# ROBOT_SENSORS.net
KiCad netlist of a schematic drawn in EasyEDA
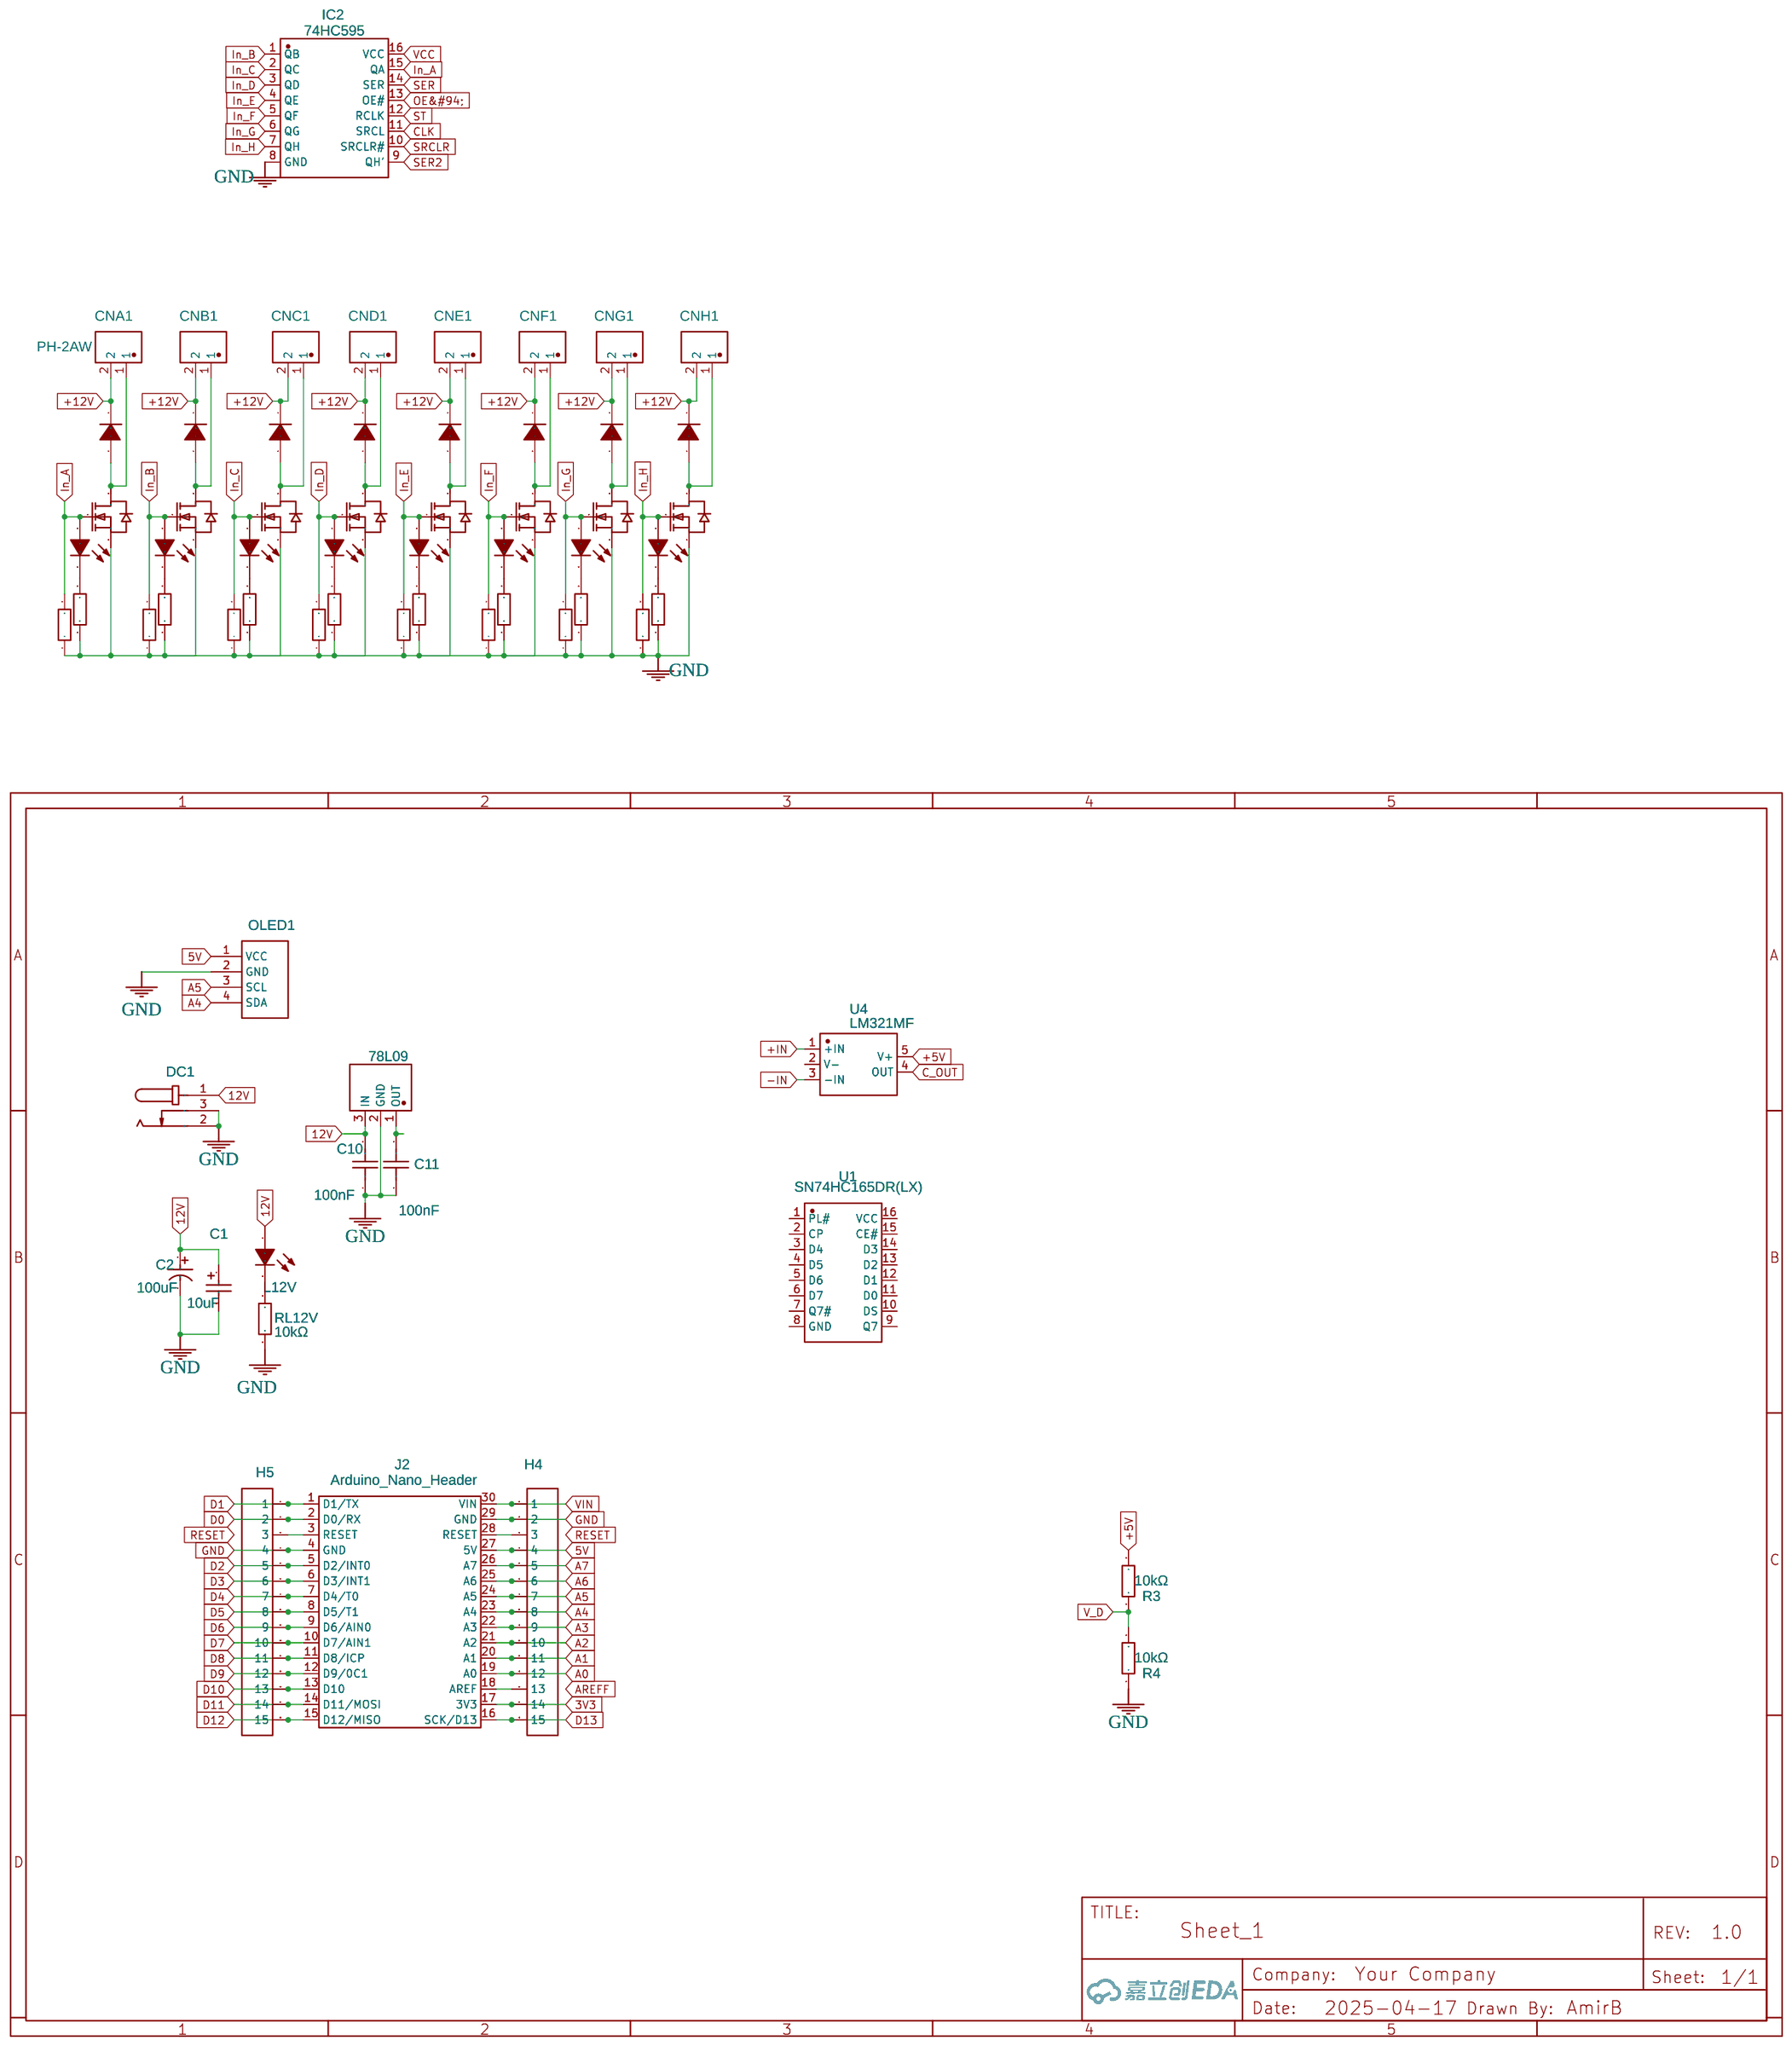
[diagram p0: schematic sheet]

(export (version "E")
  (design (tool "Eeschema 10.0.6"))
  (components
    (comp (ref "AD1")
      (value "D")
      (fields (field (name "BOM_Manufacturer Part") "ES1J") (field (name "BOM_Supplier Part") "C115404"))
      (libsource (lib "") (part "1N4007F_3"))
    )
    (comp (ref "ALED1")
      (value "LED")
      (fields
        (field (name "BOM_Manufacturer Part") "19-217/BHC-ZL1M2RY/3T")
        (field (name "BOM_Supplier Part") "C72041")
      )
      (libsource (lib "") (part "19-217/BHC-ZL1M2RY/3T_2"))
    )
    (comp (ref "AQ1")
      (value "Q")
      (fields (field (name "BOM_Manufacturer Part") "AO3400") (field (name "BOM_Supplier Part") "C5224189"))
      (libsource (lib "") (part "JSM2302_3"))
    )
    (comp (ref "AR1")
      (value "R10K")
      (fields
        (field (name "BOM_Manufacturer Part") "0603WAF1002T5E")
        (field (name "BOM_Supplier Part") "C25804")
      )
      (libsource (lib "") (part "0603WAF1001T5E_7"))
    )
    (comp (ref "AR2")
      (value "R10K")
      (fields
        (field (name "BOM_Manufacturer Part") "0603WAF1002T5E")
        (field (name "BOM_Supplier Part") "C25804")
      )
      (libsource (lib "") (part "0603WAF1001T5E_7"))
    )
    (comp (ref "BD1")
      (value "D")
      (fields (field (name "BOM_Manufacturer Part") "ES1J") (field (name "BOM_Supplier Part") "C115404"))
      (libsource (lib "") (part "1N4007F_2"))
    )
    (comp (ref "BLED1")
      (value "LED")
      (fields
        (field (name "BOM_Manufacturer Part") "19-217/BHC-ZL1M2RY/3T")
        (field (name "BOM_Supplier Part") "C72041")
      )
      (libsource (lib "") (part "19-217/BHC-ZL1M2RY/3T_7"))
    )
    (comp (ref "BQ1")
      (value "Q")
      (fields (field (name "BOM_Manufacturer Part") "AO3400") (field (name "BOM_Supplier Part") "C5224189"))
      (libsource (lib "") (part "JSM2302"))
    )
    (comp (ref "BR1")
      (value "R10K")
      (fields
        (field (name "BOM_Manufacturer Part") "0603WAF1002T5E")
        (field (name "BOM_Supplier Part") "C25804")
      )
      (libsource (lib "") (part "0603WAF1001T5E_5"))
    )
    (comp (ref "BR2")
      (value "R10K")
      (fields
        (field (name "BOM_Manufacturer Part") "0603WAF1002T5E")
        (field (name "BOM_Supplier Part") "C25804")
      )
      (libsource (lib "") (part "0603WAF1001T5E_5"))
    )
    (comp (ref "C1")
      (value "10uF")
      (fields (field (name "Manufacturer Part") "TAJA106K016RNJ") (field (name "Manufacturer") "Kyocera AVX"))
      (libsource (lib "") (part "TAJA106K016RNJ"))
    )
    (comp (ref "C2")
      (value "100uF")
      (fields
        (field (name "Manufacturer Part") "KM107M035E11RR0VH2FP0")
        (field (name "Manufacturer") "CX(承兴)")
      )
      (libsource (lib "") (part "100uF 35V 6.3*11"))
    )
    (comp (ref "C10")
      (value "100nF")
      (fields
        (field (name "Manufacturer Part") "CC0603KRX7R9BB104")
        (field (name "Manufacturer") "YAGEO(国巨)")
      )
      (libsource (lib "") (part "CC0603KRX7R9BB104"))
    )
    (comp (ref "C11")
      (value "100nF")
      (fields
        (field (name "Manufacturer Part") "CC0603KRX7R9BB104")
        (field (name "Manufacturer") "YAGEO(国巨)")
      )
      (libsource (lib "") (part "CC0603KRX7R9BB104"))
    )
    (comp (ref "CD1")
      (value "D")
      (fields (field (name "BOM_Manufacturer Part") "ES1J") (field (name "BOM_Supplier Part") "C115404"))
      (libsource (lib "") (part "1N4007F_4"))
    )
    (comp (ref "CLED1")
      (value "LED")
      (fields
        (field (name "BOM_Manufacturer Part") "19-217/BHC-ZL1M2RY/3T")
        (field (name "BOM_Supplier Part") "C72041")
      )
      (libsource (lib "") (part "19-217/BHC-ZL1M2RY/3T_8"))
    )
    (comp (ref "CNA1")
      (value "PH-2AW")
      (fields (field (name "Manufacturer") "CAX(创都)"))
      (libsource (lib "") (part "PH-2AW_1"))
    )
    (comp (ref "CNB1")
      (value "PH-2AW")
      (fields (field (name "Manufacturer") "CAX(创都)"))
      (libsource (lib "") (part "PH-2AW_6"))
    )
    (comp (ref "CNC1")
      (value "PH-2AW")
      (fields (field (name "Manufacturer") "CAX(创都)"))
      (libsource (lib "") (part "PH-2AW_5"))
    )
    (comp (ref "CND1")
      (value "PH-2AW")
      (fields (field (name "Manufacturer") "CAX(创都)"))
      (libsource (lib "") (part "PH-2AW_3"))
    )
    (comp (ref "CNE1")
      (value "PH-2AW")
      (fields (field (name "Manufacturer") "CAX(创都)"))
      (libsource (lib "") (part "PH-2AW_2"))
    )
    (comp (ref "CNF1")
      (value "PH-2AW")
      (fields (field (name "Manufacturer") "CAX(创都)"))
      (libsource (lib "") (part "PH-2AW_7"))
    )
    (comp (ref "CNG1")
      (value "PH-2AW")
      (fields (field (name "Manufacturer") "CAX(创都)"))
      (libsource (lib "") (part "PH-2AW_4"))
    )
    (comp (ref "CNH1")
      (value "PH-2AW")
      (fields (field (name "Manufacturer") "CAX(创都)"))
      (libsource (lib "") (part "PH-2AW"))
    )
    (comp (ref "CQ1")
      (value "Q")
      (fields (field (name "BOM_Manufacturer Part") "AO3400") (field (name "BOM_Supplier Part") "C5224189"))
      (libsource (lib "") (part "JSM2302_5"))
    )
    (comp (ref "CR1")
      (value "R10K")
      (fields
        (field (name "BOM_Manufacturer Part") "0603WAF1002T5E")
        (field (name "BOM_Supplier Part") "C25804")
      )
      (libsource (lib "") (part "0603WAF1001T5E_6"))
    )
    (comp (ref "CR2")
      (value "R10K")
      (fields
        (field (name "BOM_Manufacturer Part") "0603WAF1002T5E")
        (field (name "BOM_Supplier Part") "C25804")
      )
      (libsource (lib "") (part "0603WAF1001T5E_6"))
    )
    (comp (ref "DC1")
      (value "DC")
      (fields
        (field (name "BOM_Manufacturer Part") "DC005-2.0MM")
        (field (name "BOM_Supplier Part") "C111567")
      )
      (libsource (lib "") (part "DC005-2.0MM"))
    )
    (comp (ref "DD1")
      (value "D")
      (fields (field (name "BOM_Manufacturer Part") "ES1J") (field (name "BOM_Supplier Part") "C115404"))
      (libsource (lib "") (part "1N4007F_6"))
    )
    (comp (ref "DLED1")
      (value "LED")
      (fields
        (field (name "BOM_Manufacturer Part") "19-217/BHC-ZL1M2RY/3T")
        (field (name "BOM_Supplier Part") "C72041")
      )
      (libsource (lib "") (part "19-217/BHC-ZL1M2RY/3T_4"))
    )
    (comp (ref "DQ1")
      (value "Q")
      (fields (field (name "BOM_Manufacturer Part") "AO3400") (field (name "BOM_Supplier Part") "C5224189"))
      (libsource (lib "") (part "JSM2302_2"))
    )
    (comp (ref "DR1")
      (value "R10K")
      (fields
        (field (name "BOM_Manufacturer Part") "0603WAF1002T5E")
        (field (name "BOM_Supplier Part") "C25804")
      )
      (libsource (lib "") (part "0603WAF1001T5E_4"))
    )
    (comp (ref "DR2")
      (value "R10K")
      (fields
        (field (name "BOM_Manufacturer Part") "0603WAF1002T5E")
        (field (name "BOM_Supplier Part") "C25804")
      )
      (libsource (lib "") (part "0603WAF1001T5E_4"))
    )
    (comp (ref "ED1")
      (value "D")
      (fields (field (name "BOM_Manufacturer Part") "ES1J") (field (name "BOM_Supplier Part") "C115404"))
      (libsource (lib "") (part "1N4007F_1"))
    )
    (comp (ref "ELED1")
      (value "LED")
      (fields
        (field (name "BOM_Manufacturer Part") "19-217/BHC-ZL1M2RY/3T")
        (field (name "BOM_Supplier Part") "C72041")
      )
      (libsource (lib "") (part "19-217/BHC-ZL1M2RY/3T_5"))
    )
    (comp (ref "EQ1")
      (value "Q")
      (fields (field (name "BOM_Manufacturer Part") "AO3400") (field (name "BOM_Supplier Part") "C5224189"))
      (libsource (lib "") (part "JSM2302_1"))
    )
    (comp (ref "ER1")
      (value "R10K")
      (fields
        (field (name "BOM_Manufacturer Part") "0603WAF1002T5E")
        (field (name "BOM_Supplier Part") "C25804")
      )
      (libsource (lib "") (part "0603WAF1001T5E_1"))
    )
    (comp (ref "ER2")
      (value "R10K")
      (fields
        (field (name "BOM_Manufacturer Part") "0603WAF1002T5E")
        (field (name "BOM_Supplier Part") "C25804")
      )
      (libsource (lib "") (part "0603WAF1001T5E_1"))
    )
    (comp (ref "FD1")
      (value "D")
      (fields (field (name "BOM_Manufacturer Part") "ES1J") (field (name "BOM_Supplier Part") "C115404"))
      (libsource (lib "") (part "1N4007F_5"))
    )
    (comp (ref "FLED1")
      (value "LED")
      (fields
        (field (name "BOM_Manufacturer Part") "19-217/BHC-ZL1M2RY/3T")
        (field (name "BOM_Supplier Part") "C72041")
      )
      (libsource (lib "") (part "19-217/BHC-ZL1M2RY/3T"))
    )
    (comp (ref "FQ1")
      (value "Q")
      (fields (field (name "BOM_Manufacturer Part") "AO3400") (field (name "BOM_Supplier Part") "C5224189"))
      (libsource (lib "") (part "JSM2302_4"))
    )
    (comp (ref "FR1")
      (value "R10K")
      (fields
        (field (name "BOM_Manufacturer Part") "0603WAF1002T5E")
        (field (name "BOM_Supplier Part") "C25804")
      )
      (libsource (lib "") (part "0603WAF1001T5E_2"))
    )
    (comp (ref "FR2")
      (value "R10K")
      (fields
        (field (name "BOM_Manufacturer Part") "0603WAF1002T5E")
        (field (name "BOM_Supplier Part") "C25804")
      )
      (libsource (lib "") (part "0603WAF1001T5E_2"))
    )
    (comp (ref "GD1")
      (value "D")
      (fields (field (name "BOM_Manufacturer Part") "ES1J") (field (name "BOM_Supplier Part") "C115404"))
      (libsource (lib "") (part "1N4007F_7"))
    )
    (comp (ref "GLED1")
      (value "LED")
      (fields
        (field (name "BOM_Manufacturer Part") "19-217/BHC-ZL1M2RY/3T")
        (field (name "BOM_Supplier Part") "C72041")
      )
      (libsource (lib "") (part "19-217/BHC-ZL1M2RY/3T_6"))
    )
    (comp (ref "GQ1")
      (value "Q")
      (fields (field (name "BOM_Manufacturer Part") "AO3400") (field (name "BOM_Supplier Part") "C5224189"))
      (libsource (lib "") (part "JSM2302_6"))
    )
    (comp (ref "GR1")
      (value "R10K")
      (fields
        (field (name "BOM_Manufacturer Part") "0603WAF1002T5E")
        (field (name "BOM_Supplier Part") "C25804")
      )
      (libsource (lib "") (part "0603WAF1001T5E_3"))
    )
    (comp (ref "GR2")
      (value "R10K")
      (fields
        (field (name "BOM_Manufacturer Part") "0603WAF1002T5E")
        (field (name "BOM_Supplier Part") "C25804")
      )
      (libsource (lib "") (part "0603WAF1001T5E_3"))
    )
    (comp (ref "H4")
      (value "HDR-F-2.54_1x15")
      (fields (field (name "BOM_Supplier Part") "C124408"))
      (libsource (lib "") (part "HDR-F-2.54_1x15"))
    )
    (comp (ref "H5")
      (value "HDR-F-2.54_1x15")
      (fields (field (name "BOM_Supplier Part") "C124408"))
      (libsource (lib "") (part "HDR-F-2.54_1x15_1"))
    )
    (comp (ref "HD1")
      (value "D")
      (fields (field (name "BOM_Manufacturer Part") "ES1J") (field (name "BOM_Supplier Part") "C115404"))
      (libsource (lib "") (part "1N4007F"))
    )
    (comp (ref "HLED1")
      (value "LED")
      (fields
        (field (name "BOM_Manufacturer Part") "19-217/BHC-ZL1M2RY/3T")
        (field (name "BOM_Supplier Part") "C72041")
      )
      (libsource (lib "") (part "19-217/BHC-ZL1M2RY/3T_3"))
    )
    (comp (ref "HQ1")
      (value "Q")
      (fields (field (name "BOM_Manufacturer Part") "AO3400") (field (name "BOM_Supplier Part") "C5224189"))
      (libsource (lib "") (part "JSM2302_7"))
    )
    (comp (ref "HR1")
      (value "R10K")
      (fields
        (field (name "BOM_Manufacturer Part") "0603WAF1002T5E")
        (field (name "BOM_Supplier Part") "C25804")
      )
      (libsource (lib "") (part "0603WAF1001T5E"))
    )
    (comp (ref "HR2")
      (value "R10K")
      (fields
        (field (name "BOM_Manufacturer Part") "0603WAF1002T5E")
        (field (name "BOM_Supplier Part") "C25804")
      )
      (libsource (lib "") (part "0603WAF1001T5E"))
    )
    (comp (ref "IC2")
      (value "74HC595")
      (fields
        (field (name "BOM_Manufacturer Part") "U74HC595AG-S16-R")
        (field (name "BOM_Supplier Part") "C87300")
      )
      (libsource (lib "") (part "U74HC595AG-S16-R"))
    )
    (comp (ref "J2") (value "Arduino_Nano_Header") (libsource (lib "") (part "Arduino_Nano_Header")))
    (comp (ref "L12V")
      (value "LED")
      (fields
        (field (name "BOM_Manufacturer Part") "19-217/BHC-ZL1M2RY/3T")
        (field (name "BOM_Supplier Part") "C72041")
      )
      (libsource (lib "") (part "19-217/BHC-ZL1M2RY/3T_1"))
    )
    (comp (ref "OLED1")
      (value "1.3 inch OLED SSH1106 I2C 128x64 copy")
      (libsource (lib "") (part "1.3 inch OLED SSH1106 I2C 128x64 copy"))
    )
    (comp (ref "R3")
      (value "10kΩ")
      (fields
        (field (name "Manufacturer Part") "0603WAF1002T5E")
        (field (name "Manufacturer") "UNI-ROYAL(厚声)")
      )
      (libsource (lib "") (part "0603WAF1002T5E"))
    )
    (comp (ref "R4")
      (value "10kΩ")
      (fields
        (field (name "Manufacturer Part") "0603WAF1002T5E")
        (field (name "Manufacturer") "UNI-ROYAL(厚声)")
      )
      (libsource (lib "") (part "0603WAF1002T5E"))
    )
    (comp (ref "RL12V")
      (value "10kΩ")
      (fields
        (field (name "BOM_Manufacturer Part") "0603WAF1002T5E")
        (field (name "BOM_Supplier Part") "C25804")
      )
      (libsource (lib "") (part "0603WAF1002T5E_1"))
    )
    (comp (ref "U1")
      (value "SN74HC165DR(LX)")
      (fields (field (name "Manufacturer") "LX(灵星芯微)"))
      (libsource (lib "") (part "SN74HC165DR(LX)"))
    )
    (comp (ref "U4")
      (value "LM321MF")
      (fields (field (name "Manufacturer") "UMW(友台半导体)"))
      (libsource (lib "") (part "LM321MF"))
    )
    (comp (ref "U5")
      (value "78L09")
      (fields (field (name "Manufacturer Part") "78L09U 78L09") (field (name "Manufacturer") "CBI(创基)"))
      (libsource (lib "") (part "78L09U 78L09"))
    )
  )
  (nets
    (net (code "1") (name "+5V") (class "Default")
      (node (ref "R3") (pin "2") (pinfunction "2_2") (pintype "input"))
      (node (ref "U4") (pin "5") (pinfunction "V+_5") (pintype "unspecified"))
    )
    (net (code "2") (name "+12V") (class "Default")
      (node (ref "AD1") (pin "1") (pinfunction "C_1") (pintype "unspecified"))
      (node (ref "BD1") (pin "1") (pinfunction "C_1") (pintype "unspecified"))
      (node (ref "CD1") (pin "1") (pinfunction "C_1") (pintype "unspecified"))
      (node (ref "CNA1") (pin "2") (pinfunction "2_2") (pintype "unspecified"))
      (node (ref "CNB1") (pin "2") (pinfunction "2_2") (pintype "unspecified"))
      (node (ref "CNC1") (pin "2") (pinfunction "2_2") (pintype "unspecified"))
      (node (ref "CND1") (pin "2") (pinfunction "2_2") (pintype "unspecified"))
      (node (ref "CNE1") (pin "2") (pinfunction "2_2") (pintype "unspecified"))
      (node (ref "CNF1") (pin "2") (pinfunction "2_2") (pintype "unspecified"))
      (node (ref "CNG1") (pin "2") (pinfunction "2_2") (pintype "unspecified"))
      (node (ref "CNH1") (pin "2") (pinfunction "2_2") (pintype "unspecified"))
      (node (ref "DD1") (pin "1") (pinfunction "C_1") (pintype "unspecified"))
      (node (ref "ED1") (pin "1") (pinfunction "C_1") (pintype "unspecified"))
      (node (ref "FD1") (pin "1") (pinfunction "C_1") (pintype "unspecified"))
      (node (ref "GD1") (pin "1") (pinfunction "C_1") (pintype "unspecified"))
      (node (ref "HD1") (pin "1") (pinfunction "C_1") (pintype "unspecified"))
    )
    (net (code "3") (name "+IN") (class "Default")
      (node (ref "U4") (pin "1") (pinfunction "+IN_1") (pintype "unspecified"))
    )
    (net (code "4") (name "-IN") (class "Default")
      (node (ref "U4") (pin "3") (pinfunction "-IN_3") (pintype "unspecified"))
    )
    (net (code "5") (name "3V3") (class "Default")
      (node (ref "H4") (pin "14") (pinfunction "14_14") (pintype "unspecified"))
      (node (ref "J2") (pin "17") (pinfunction "3V3_17") (pintype "unspecified"))
    )
    (net (code "6") (name "5V") (class "Default")
      (node (ref "H4") (pin "4") (pinfunction "4_4") (pintype "unspecified"))
      (node (ref "J2") (pin "27") (pinfunction "5V_27") (pintype "unspecified"))
      (node (ref "OLED1") (pin "1") (pinfunction "VCC_1") (pintype "passive"))
    )
    (net (code "7") (name "12V") (class "Default")
      (node (ref "C1") (pin "1") (pinfunction "1_1") (pintype "input"))
      (node (ref "C10") (pin "2") (pinfunction "2_2") (pintype "unspecified"))
      (node (ref "C2") (pin "1") (pinfunction "1_1") (pintype "input"))
      (node (ref "DC1") (pin "1") (pinfunction "1_1") (pintype "unspecified"))
      (node (ref "L12V") (pin "1") (pinfunction "A_1") (pintype "input"))
      (node (ref "U5") (pin "3") (pinfunction "IN_3") (pintype "unspecified"))
    )
    (net (code "8") (name "A0") (class "Default")
      (node (ref "H4") (pin "12") (pinfunction "12_12") (pintype "unspecified"))
      (node (ref "J2") (pin "19") (pinfunction "A0_19") (pintype "unspecified"))
    )
    (net (code "9") (name "A1") (class "Default")
      (node (ref "H4") (pin "11") (pinfunction "11_11") (pintype "unspecified"))
      (node (ref "J2") (pin "20") (pinfunction "A1_20") (pintype "unspecified"))
    )
    (net (code "10") (name "A2") (class "Default")
      (node (ref "H4") (pin "10") (pinfunction "10_10") (pintype "unspecified"))
      (node (ref "J2") (pin "21") (pinfunction "A2_21") (pintype "unspecified"))
    )
    (net (code "11") (name "A3") (class "Default")
      (node (ref "H4") (pin "9") (pinfunction "9_9") (pintype "unspecified"))
      (node (ref "J2") (pin "22") (pinfunction "A3_22") (pintype "unspecified"))
    )
    (net (code "12") (name "A4") (class "Default")
      (node (ref "H4") (pin "8") (pinfunction "8_8") (pintype "unspecified"))
      (node (ref "J2") (pin "23") (pinfunction "A4_23") (pintype "unspecified"))
      (node (ref "OLED1") (pin "4") (pinfunction "SDA_4") (pintype "bidirectional"))
    )
    (net (code "13") (name "A5") (class "Default")
      (node (ref "H4") (pin "7") (pinfunction "7_7") (pintype "unspecified"))
      (node (ref "J2") (pin "24") (pinfunction "A5_24") (pintype "unspecified"))
      (node (ref "OLED1") (pin "3") (pinfunction "SCL_3") (pintype "bidirectional"))
    )
    (net (code "14") (name "A6") (class "Default")
      (node (ref "H4") (pin "6") (pinfunction "6_6") (pintype "unspecified"))
      (node (ref "J2") (pin "25") (pinfunction "A6_25") (pintype "unspecified"))
    )
    (net (code "15") (name "A7") (class "Default")
      (node (ref "H4") (pin "5") (pinfunction "5_5") (pintype "unspecified"))
      (node (ref "J2") (pin "26") (pinfunction "A7_26") (pintype "unspecified"))
    )
    (net (code "17") (name "CLK") (class "Default")
      (node (ref "IC2") (pin "11") (pinfunction "SRCL_11") (pintype "unspecified"))
    )
    (net (code "18") (name "C_OUT") (class "Default")
      (node (ref "U4") (pin "4") (pinfunction "OUT_4") (pintype "unspecified"))
    )
    (net (code "19") (name "D0") (class "Default")
      (node (ref "H5") (pin "2") (pinfunction "2_2") (pintype "unspecified"))
      (node (ref "J2") (pin "2") (pinfunction "D0/RX_2") (pintype "unspecified"))
    )
    (net (code "20") (name "D1") (class "Default")
      (node (ref "H5") (pin "1") (pinfunction "1_1") (pintype "unspecified"))
      (node (ref "J2") (pin "1") (pinfunction "D1/TX_1") (pintype "unspecified"))
    )
    (net (code "21") (name "D2") (class "Default")
      (node (ref "H5") (pin "5") (pinfunction "5_5") (pintype "unspecified"))
      (node (ref "J2") (pin "5") (pinfunction "D2/INT0_5") (pintype "unspecified"))
    )
    (net (code "22") (name "D3") (class "Default")
      (node (ref "H5") (pin "6") (pinfunction "6_6") (pintype "unspecified"))
      (node (ref "J2") (pin "6") (pinfunction "D3/INT1_6") (pintype "unspecified"))
    )
    (net (code "23") (name "D4") (class "Default")
      (node (ref "H5") (pin "7") (pinfunction "7_7") (pintype "unspecified"))
      (node (ref "J2") (pin "7") (pinfunction "D4/T0_7") (pintype "unspecified"))
    )
    (net (code "24") (name "D5") (class "Default")
      (node (ref "H5") (pin "8") (pinfunction "8_8") (pintype "unspecified"))
      (node (ref "J2") (pin "8") (pinfunction "D5/T1_8") (pintype "unspecified"))
    )
    (net (code "25") (name "D6") (class "Default")
      (node (ref "H5") (pin "9") (pinfunction "9_9") (pintype "unspecified"))
      (node (ref "J2") (pin "9") (pinfunction "D6/AIN0_9") (pintype "unspecified"))
    )
    (net (code "26") (name "D7") (class "Default")
      (node (ref "H5") (pin "10") (pinfunction "10_10") (pintype "unspecified"))
      (node (ref "J2") (pin "10") (pinfunction "D7/AIN1_10") (pintype "unspecified"))
    )
    (net (code "27") (name "D8") (class "Default")
      (node (ref "H5") (pin "11") (pinfunction "11_11") (pintype "unspecified"))
      (node (ref "J2") (pin "11") (pinfunction "D8/ICP_11") (pintype "unspecified"))
    )
    (net (code "28") (name "D9") (class "Default")
      (node (ref "H5") (pin "12") (pinfunction "12_12") (pintype "unspecified"))
      (node (ref "J2") (pin "12") (pinfunction "D9/0C1_12") (pintype "unspecified"))
    )
    (net (code "29") (name "D10") (class "Default")
      (node (ref "H5") (pin "13") (pinfunction "13_13") (pintype "unspecified"))
      (node (ref "J2") (pin "13") (pinfunction "D10_13") (pintype "unspecified"))
    )
    (net (code "30") (name "D11") (class "Default")
      (node (ref "H5") (pin "14") (pinfunction "14_14") (pintype "unspecified"))
      (node (ref "J2") (pin "14") (pinfunction "D11/MOSI_14") (pintype "unspecified"))
    )
    (net (code "31") (name "D12") (class "Default")
      (node (ref "H5") (pin "15") (pinfunction "15_15") (pintype "unspecified"))
      (node (ref "J2") (pin "15") (pinfunction "D12/MISO_15") (pintype "unspecified"))
    )
    (net (code "32") (name "D13") (class "Default")
      (node (ref "H4") (pin "15") (pinfunction "15_15") (pintype "unspecified"))
      (node (ref "J2") (pin "16") (pinfunction "SCK/D13_16") (pintype "unspecified"))
    )
    (net (code "33") (name "GND") (class "Default")
      (node (ref "AQ1") (pin "2") (pinfunction "S_2") (pintype "unspecified"))
      (node (ref "AR1") (pin "1") (pinfunction "1_1") (pintype "input"))
      (node (ref "AR2") (pin "1") (pinfunction "1_1") (pintype "input"))
      (node (ref "BQ1") (pin "2") (pinfunction "S_2") (pintype "unspecified"))
      (node (ref "BR1") (pin "1") (pinfunction "1_1") (pintype "input"))
      (node (ref "BR2") (pin "1") (pinfunction "1_1") (pintype "input"))
      (node (ref "C1") (pin "2") (pinfunction "2_2") (pintype "input"))
      (node (ref "C10") (pin "1") (pinfunction "1_1") (pintype "unspecified"))
      (node (ref "C11") (pin "1") (pinfunction "1_1") (pintype "unspecified"))
      (node (ref "C2") (pin "2") (pinfunction "2_2") (pintype "input"))
      (node (ref "CQ1") (pin "2") (pinfunction "S_2") (pintype "unspecified"))
      (node (ref "CR1") (pin "1") (pinfunction "1_1") (pintype "input"))
      (node (ref "CR2") (pin "1") (pinfunction "1_1") (pintype "input"))
      (node (ref "DC1") (pin "2") (pinfunction "2_2") (pintype "unspecified"))
      (node (ref "DC1") (pin "3") (pinfunction "3_3") (pintype "unspecified"))
      (node (ref "DQ1") (pin "2") (pinfunction "S_2") (pintype "unspecified"))
      (node (ref "DR1") (pin "1") (pinfunction "1_1") (pintype "input"))
      (node (ref "DR2") (pin "1") (pinfunction "1_1") (pintype "input"))
      (node (ref "EQ1") (pin "2") (pinfunction "S_2") (pintype "unspecified"))
      (node (ref "ER1") (pin "1") (pinfunction "1_1") (pintype "input"))
      (node (ref "ER2") (pin "1") (pinfunction "1_1") (pintype "input"))
      (node (ref "FQ1") (pin "2") (pinfunction "S_2") (pintype "unspecified"))
      (node (ref "FR1") (pin "1") (pinfunction "1_1") (pintype "input"))
      (node (ref "FR2") (pin "1") (pinfunction "1_1") (pintype "input"))
      (node (ref "GQ1") (pin "2") (pinfunction "S_2") (pintype "unspecified"))
      (node (ref "GR1") (pin "1") (pinfunction "1_1") (pintype "input"))
      (node (ref "GR2") (pin "1") (pinfunction "1_1") (pintype "input"))
      (node (ref "H4") (pin "2") (pinfunction "2_2") (pintype "unspecified"))
      (node (ref "H5") (pin "4") (pinfunction "4_4") (pintype "unspecified"))
      (node (ref "HQ1") (pin "2") (pinfunction "S_2") (pintype "unspecified"))
      (node (ref "HR1") (pin "1") (pinfunction "1_1") (pintype "input"))
      (node (ref "HR2") (pin "1") (pinfunction "1_1") (pintype "input"))
      (node (ref "IC2") (pin "8") (pinfunction "GND_8") (pintype "unspecified"))
      (node (ref "J2") (pin "29") (pinfunction "GND_29") (pintype "unspecified"))
      (node (ref "J2") (pin "4") (pinfunction "GND_4") (pintype "unspecified"))
      (node (ref "OLED1") (pin "2") (pinfunction "GND_2") (pintype "passive"))
      (node (ref "R4") (pin "1") (pinfunction "1_1") (pintype "input"))
      (node (ref "RL12V") (pin "2") (pinfunction "2_2") (pintype "input"))
      (node (ref "U5") (pin "2") (pinfunction "GND_2") (pintype "unspecified"))
    )
    (net (code "34") (name "In_A") (class "Default")
      (node (ref "ALED1") (pin "1") (pinfunction "A_1") (pintype "input"))
      (node (ref "AQ1") (pin "1") (pinfunction "G_1") (pintype "unspecified"))
      (node (ref "AR1") (pin "2") (pinfunction "2_2") (pintype "input"))
      (node (ref "IC2") (pin "15") (pinfunction "QA_15") (pintype "unspecified"))
    )
    (net (code "35") (name "In_B") (class "Default")
      (node (ref "BLED1") (pin "1") (pinfunction "A_1") (pintype "input"))
      (node (ref "BQ1") (pin "1") (pinfunction "G_1") (pintype "unspecified"))
      (node (ref "BR1") (pin "2") (pinfunction "2_2") (pintype "input"))
      (node (ref "IC2") (pin "1") (pinfunction "QB_1") (pintype "unspecified"))
    )
    (net (code "36") (name "In_C") (class "Default")
      (node (ref "CLED1") (pin "1") (pinfunction "A_1") (pintype "input"))
      (node (ref "CQ1") (pin "1") (pinfunction "G_1") (pintype "unspecified"))
      (node (ref "CR1") (pin "2") (pinfunction "2_2") (pintype "input"))
      (node (ref "IC2") (pin "2") (pinfunction "QC_2") (pintype "unspecified"))
    )
    (net (code "37") (name "In_D") (class "Default")
      (node (ref "DLED1") (pin "1") (pinfunction "A_1") (pintype "input"))
      (node (ref "DQ1") (pin "1") (pinfunction "G_1") (pintype "unspecified"))
      (node (ref "DR1") (pin "2") (pinfunction "2_2") (pintype "input"))
      (node (ref "IC2") (pin "3") (pinfunction "QD_3") (pintype "unspecified"))
    )
    (net (code "38") (name "In_E") (class "Default")
      (node (ref "ELED1") (pin "1") (pinfunction "A_1") (pintype "input"))
      (node (ref "EQ1") (pin "1") (pinfunction "G_1") (pintype "unspecified"))
      (node (ref "ER1") (pin "2") (pinfunction "2_2") (pintype "input"))
      (node (ref "IC2") (pin "4") (pinfunction "QE_4") (pintype "unspecified"))
    )
    (net (code "39") (name "In_F") (class "Default")
      (node (ref "FLED1") (pin "1") (pinfunction "A_1") (pintype "input"))
      (node (ref "FQ1") (pin "1") (pinfunction "G_1") (pintype "unspecified"))
      (node (ref "FR1") (pin "2") (pinfunction "2_2") (pintype "input"))
      (node (ref "IC2") (pin "5") (pinfunction "QF_5") (pintype "unspecified"))
    )
    (net (code "40") (name "In_G") (class "Default")
      (node (ref "GLED1") (pin "1") (pinfunction "A_1") (pintype "input"))
      (node (ref "GQ1") (pin "1") (pinfunction "G_1") (pintype "unspecified"))
      (node (ref "GR1") (pin "2") (pinfunction "2_2") (pintype "input"))
      (node (ref "IC2") (pin "6") (pinfunction "QG_6") (pintype "unspecified"))
    )
    (net (code "41") (name "In_H") (class "Default")
      (node (ref "HLED1") (pin "1") (pinfunction "A_1") (pintype "input"))
      (node (ref "HQ1") (pin "1") (pinfunction "G_1") (pintype "unspecified"))
      (node (ref "HR1") (pin "2") (pinfunction "2_2") (pintype "input"))
      (node (ref "IC2") (pin "7") (pinfunction "QH_7") (pintype "unspecified"))
    )
    (net (code "42") (name "Net-(AD1-A)") (class "Default")
      (node (ref "AD1") (pin "2") (pinfunction "A_2") (pintype "unspecified"))
      (node (ref "AQ1") (pin "3") (pinfunction "D_3") (pintype "unspecified"))
      (node (ref "CNA1") (pin "1") (pinfunction "1_1") (pintype "unspecified"))
    )
    (net (code "43") (name "Net-(ALED1-C)") (class "Default")
      (node (ref "ALED1") (pin "2") (pinfunction "C_2") (pintype "input"))
      (node (ref "AR2") (pin "2") (pinfunction "2_2") (pintype "input"))
    )
    (net (code "44") (name "Net-(BD1-A)") (class "Default")
      (node (ref "BD1") (pin "2") (pinfunction "A_2") (pintype "unspecified"))
      (node (ref "BQ1") (pin "3") (pinfunction "D_3") (pintype "unspecified"))
      (node (ref "CNB1") (pin "1") (pinfunction "1_1") (pintype "unspecified"))
    )
    (net (code "45") (name "Net-(BLED1-C)") (class "Default")
      (node (ref "BLED1") (pin "2") (pinfunction "C_2") (pintype "input"))
      (node (ref "BR2") (pin "2") (pinfunction "2_2") (pintype "input"))
    )
    (net (code "46") (name "Net-(CD1-A)") (class "Default")
      (node (ref "CD1") (pin "2") (pinfunction "A_2") (pintype "unspecified"))
      (node (ref "CNC1") (pin "1") (pinfunction "1_1") (pintype "unspecified"))
      (node (ref "CQ1") (pin "3") (pinfunction "D_3") (pintype "unspecified"))
    )
    (net (code "47") (name "Net-(CLED1-C)") (class "Default")
      (node (ref "CLED1") (pin "2") (pinfunction "C_2") (pintype "input"))
      (node (ref "CR2") (pin "2") (pinfunction "2_2") (pintype "input"))
    )
    (net (code "48") (name "Net-(DD1-A)") (class "Default")
      (node (ref "CND1") (pin "1") (pinfunction "1_1") (pintype "unspecified"))
      (node (ref "DD1") (pin "2") (pinfunction "A_2") (pintype "unspecified"))
      (node (ref "DQ1") (pin "3") (pinfunction "D_3") (pintype "unspecified"))
    )
    (net (code "49") (name "Net-(DLED1-C)") (class "Default")
      (node (ref "DLED1") (pin "2") (pinfunction "C_2") (pintype "input"))
      (node (ref "DR2") (pin "2") (pinfunction "2_2") (pintype "input"))
    )
    (net (code "50") (name "Net-(ED1-A)") (class "Default")
      (node (ref "CNE1") (pin "1") (pinfunction "1_1") (pintype "unspecified"))
      (node (ref "ED1") (pin "2") (pinfunction "A_2") (pintype "unspecified"))
      (node (ref "EQ1") (pin "3") (pinfunction "D_3") (pintype "unspecified"))
    )
    (net (code "51") (name "Net-(ELED1-C)") (class "Default")
      (node (ref "ELED1") (pin "2") (pinfunction "C_2") (pintype "input"))
      (node (ref "ER2") (pin "2") (pinfunction "2_2") (pintype "input"))
    )
    (net (code "52") (name "Net-(FD1-A)") (class "Default")
      (node (ref "CNF1") (pin "1") (pinfunction "1_1") (pintype "unspecified"))
      (node (ref "FD1") (pin "2") (pinfunction "A_2") (pintype "unspecified"))
      (node (ref "FQ1") (pin "3") (pinfunction "D_3") (pintype "unspecified"))
    )
    (net (code "53") (name "Net-(FLED1-C)") (class "Default")
      (node (ref "FLED1") (pin "2") (pinfunction "C_2") (pintype "input"))
      (node (ref "FR2") (pin "2") (pinfunction "2_2") (pintype "input"))
    )
    (net (code "54") (name "Net-(GD1-A)") (class "Default")
      (node (ref "CNG1") (pin "1") (pinfunction "1_1") (pintype "unspecified"))
      (node (ref "GD1") (pin "2") (pinfunction "A_2") (pintype "unspecified"))
      (node (ref "GQ1") (pin "3") (pinfunction "D_3") (pintype "unspecified"))
    )
    (net (code "55") (name "Net-(GLED1-C)") (class "Default")
      (node (ref "GLED1") (pin "2") (pinfunction "C_2") (pintype "input"))
      (node (ref "GR2") (pin "2") (pinfunction "2_2") (pintype "input"))
    )
    (net (code "56") (name "Net-(H4-Pad3)") (class "Default")
      (node (ref "H4") (pin "3") (pinfunction "3_3") (pintype "unspecified"))
      (node (ref "J2") (pin "28") (pinfunction "RESET_28") (pintype "unspecified"))
    )
    (net (code "57") (name "Net-(H5-Pad3)") (class "Default")
      (node (ref "H5") (pin "3") (pinfunction "3_3") (pintype "unspecified"))
      (node (ref "J2") (pin "3") (pinfunction "RESET_3") (pintype "unspecified"))
    )
    (net (code "58") (name "Net-(HD1-A)") (class "Default")
      (node (ref "CNH1") (pin "1") (pinfunction "1_1") (pintype "unspecified"))
      (node (ref "HD1") (pin "2") (pinfunction "A_2") (pintype "unspecified"))
      (node (ref "HQ1") (pin "3") (pinfunction "D_3") (pintype "unspecified"))
    )
    (net (code "59") (name "Net-(HLED1-C)") (class "Default")
      (node (ref "HLED1") (pin "2") (pinfunction "C_2") (pintype "input"))
      (node (ref "HR2") (pin "2") (pinfunction "2_2") (pintype "input"))
    )
    (net (code "60") (name "Net-(J2-AREF)") (class "Default")
      (node (ref "H4") (pin "13") (pinfunction "13_13") (pintype "unspecified"))
      (node (ref "J2") (pin "18") (pinfunction "AREF_18") (pintype "unspecified"))
    )
    (net (code "61") (name "Net-(L12V-C)") (class "Default")
      (node (ref "L12V") (pin "2") (pinfunction "C_2") (pintype "input"))
      (node (ref "RL12V") (pin "1") (pinfunction "1_1") (pintype "input"))
    )
    (net (code "62") (name "Net-(U5-OUT)") (class "Default")
      (node (ref "C11") (pin "2") (pinfunction "2_2") (pintype "unspecified"))
      (node (ref "U5") (pin "1") (pinfunction "OUT_1") (pintype "unspecified"))
    )
    (net (code "63") (name "OE&#94;") (class "Default")
      (node (ref "IC2") (pin "13") (pinfunction "OE#_13") (pintype "unspecified"))
    )
    (net (code "65") (name "SER") (class "Default")
      (node (ref "IC2") (pin "14") (pinfunction "SER_14") (pintype "unspecified"))
    )
    (net (code "66") (name "SER2") (class "Default")
      (node (ref "IC2") (pin "9") (pinfunction "QH'_9") (pintype "unspecified"))
    )
    (net (code "67") (name "SRCLR") (class "Default")
      (node (ref "IC2") (pin "10") (pinfunction "SRCLR#_10") (pintype "unspecified"))
    )
    (net (code "68") (name "ST") (class "Default")
      (node (ref "IC2") (pin "12") (pinfunction "RCLK_12") (pintype "unspecified"))
    )
    (net (code "69") (name "VCC") (class "Default")
      (node (ref "IC2") (pin "16") (pinfunction "VCC_16") (pintype "unspecified"))
    )
    (net (code "70") (name "VIN") (class "Default")
      (node (ref "H4") (pin "1") (pinfunction "1_1") (pintype "unspecified"))
      (node (ref "J2") (pin "30") (pinfunction "VIN_30") (pintype "unspecified"))
    )
    (net (code "71") (name "V_D") (class "Default")
      (node (ref "R3") (pin "1") (pinfunction "1_1") (pintype "input"))
      (node (ref "R4") (pin "2") (pinfunction "2_2") (pintype "input"))
    )
    (net (code "72") (name "unconnected-(U1-CE#-Pad15)") (class "Default")
      (node (ref "U1") (pin "15") (pinfunction "CE#_15") (pintype "unspecified"))
    )
    (net (code "73") (name "unconnected-(U1-CP-Pad2)") (class "Default")
      (node (ref "U1") (pin "2") (pinfunction "CP_2") (pintype "unspecified"))
    )
    (net (code "74") (name "unconnected-(U1-D0-Pad11)") (class "Default")
      (node (ref "U1") (pin "11") (pinfunction "D0_11") (pintype "unspecified"))
    )
    (net (code "75") (name "unconnected-(U1-D1-Pad12)") (class "Default")
      (node (ref "U1") (pin "12") (pinfunction "D1_12") (pintype "unspecified"))
    )
    (net (code "76") (name "unconnected-(U1-D2-Pad13)") (class "Default")
      (node (ref "U1") (pin "13") (pinfunction "D2_13") (pintype "unspecified"))
    )
    (net (code "77") (name "unconnected-(U1-D3-Pad14)") (class "Default")
      (node (ref "U1") (pin "14") (pinfunction "D3_14") (pintype "unspecified"))
    )
    (net (code "78") (name "unconnected-(U1-D4-Pad3)") (class "Default")
      (node (ref "U1") (pin "3") (pinfunction "D4_3") (pintype "unspecified"))
    )
    (net (code "79") (name "unconnected-(U1-D5-Pad4)") (class "Default")
      (node (ref "U1") (pin "4") (pinfunction "D5_4") (pintype "unspecified"))
    )
    (net (code "80") (name "unconnected-(U1-D6-Pad5)") (class "Default")
      (node (ref "U1") (pin "5") (pinfunction "D6_5") (pintype "unspecified"))
    )
    (net (code "81") (name "unconnected-(U1-D7-Pad6)") (class "Default")
      (node (ref "U1") (pin "6") (pinfunction "D7_6") (pintype "unspecified"))
    )
    (net (code "82") (name "unconnected-(U1-DS-Pad10)") (class "Default")
      (node (ref "U1") (pin "10") (pinfunction "DS_10") (pintype "unspecified"))
    )
    (net (code "83") (name "unconnected-(U1-GND-Pad8)") (class "Default")
      (node (ref "U1") (pin "8") (pinfunction "GND_8") (pintype "unspecified"))
    )
    (net (code "84") (name "unconnected-(U1-PL#-Pad1)") (class "Default")
      (node (ref "U1") (pin "1") (pinfunction "PL#_1") (pintype "unspecified"))
    )
    (net (code "85") (name "unconnected-(U1-Q7#-Pad7)") (class "Default")
      (node (ref "U1") (pin "7") (pinfunction "Q7#_7") (pintype "unspecified"))
    )
    (net (code "86") (name "unconnected-(U1-Q7-Pad9)") (class "Default")
      (node (ref "U1") (pin "9") (pinfunction "Q7_9") (pintype "unspecified"))
    )
    (net (code "87") (name "unconnected-(U1-VCC-Pad16)") (class "Default")
      (node (ref "U1") (pin "16") (pinfunction "VCC_16") (pintype "unspecified"))
    )
    (net (code "88") (name "unconnected-(U4-V--Pad2)") (class "Default")
      (node (ref "U4") (pin "2") (pinfunction "V-_2") (pintype "unspecified"))
    )
  )
)
